# microLift.net
KiCad netlist of a schematic drawn in EAGLE
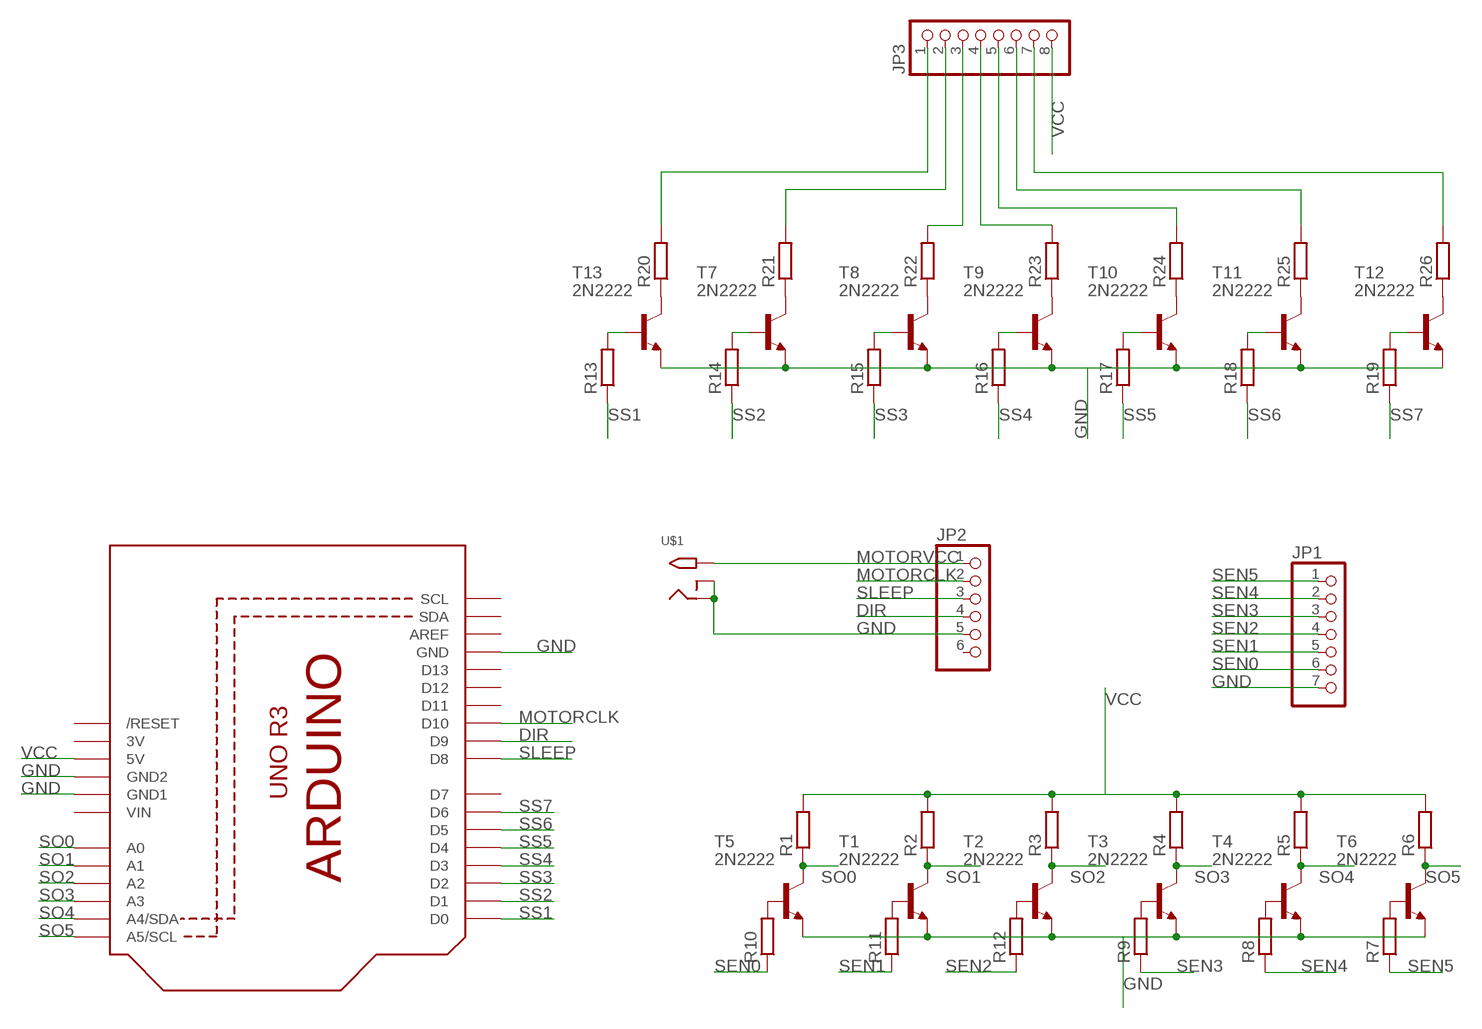
[diagram p0: schematic, sheet 1]

(export (version "E")
  (design (tool "Eeschema 10.0.6"))
  (components
    (comp (ref "JP1")
      (value "PINHD-1X7")
      (footprint "eagle-import:1X07")
      (libsource (lib "eagle-import") (part "PINHD-1X7"))
    )
    (comp (ref "JP2")
      (value "PINHD-1X6")
      (footprint "eagle-import:1X06")
      (libsource (lib "eagle-import") (part "PINHD-1X6"))
    )
    (comp (ref "JP3")
      (value "PINHD-1X8BIG")
      (footprint "eagle-import:1X08-BIG")
      (libsource (lib "eagle-import") (part "PINHD-1X8BIG"))
    )
    (comp (ref "Q1")
      (value "ARDUINOR3-NOIOREF-NOTEXT")
      (footprint "eagle-import:ARDUINOR3-NOTEXT-NOIOREF")
      (libsource (lib "eagle-import") (part "ARDUINOR3-NOIOREF-NOTEXT"))
    )
    (comp (ref "R1")
      (value "R-EU_0204/7")
      (footprint "eagle-import:0204_7")
      (libsource (lib "eagle-import") (part "R-EU_0204/7"))
    )
    (comp (ref "R2")
      (value "R-EU_0204/7")
      (footprint "eagle-import:0204_7")
      (libsource (lib "eagle-import") (part "R-EU_0204/7"))
    )
    (comp (ref "R3")
      (value "R-EU_0204/7")
      (footprint "eagle-import:0204_7")
      (libsource (lib "eagle-import") (part "R-EU_0204/7"))
    )
    (comp (ref "R4")
      (value "R-EU_0204/7")
      (footprint "eagle-import:0204_7")
      (libsource (lib "eagle-import") (part "R-EU_0204/7"))
    )
    (comp (ref "R5")
      (value "R-EU_0204/7")
      (footprint "eagle-import:0204_7")
      (libsource (lib "eagle-import") (part "R-EU_0204/7"))
    )
    (comp (ref "R6")
      (value "R-EU_0204/7")
      (footprint "eagle-import:0204_7")
      (libsource (lib "eagle-import") (part "R-EU_0204/7"))
    )
    (comp (ref "R7")
      (value "R-EU_0204/7")
      (footprint "eagle-import:0204_7")
      (libsource (lib "eagle-import") (part "resistor_R-EU_0204/7"))
    )
    (comp (ref "R8")
      (value "R-EU_0204/7")
      (footprint "eagle-import:0204_7")
      (libsource (lib "eagle-import") (part "resistor_R-EU_0204/7"))
    )
    (comp (ref "R9")
      (value "R-EU_0204/7")
      (footprint "eagle-import:0204_7")
      (libsource (lib "eagle-import") (part "resistor_R-EU_0204/7"))
    )
    (comp (ref "R10")
      (value "R-EU_0204/7")
      (footprint "eagle-import:0204_7")
      (libsource (lib "eagle-import") (part "resistor_R-EU_0204/7"))
    )
    (comp (ref "R11")
      (value "R-EU_0204/7")
      (footprint "eagle-import:0204_7")
      (libsource (lib "eagle-import") (part "resistor_R-EU_0204/7"))
    )
    (comp (ref "R12")
      (value "R-EU_0204/7")
      (footprint "eagle-import:0204_7")
      (libsource (lib "eagle-import") (part "resistor_R-EU_0204/7"))
    )
    (comp (ref "R13")
      (value "R-EU_0204/7")
      (footprint "eagle-import:0204_7")
      (libsource (lib "eagle-import") (part "R-EU_0204/7"))
    )
    (comp (ref "R14")
      (value "R-EU_0204/7")
      (footprint "eagle-import:0204_7")
      (libsource (lib "eagle-import") (part "R-EU_0204/7"))
    )
    (comp (ref "R15")
      (value "R-EU_0204/7")
      (footprint "eagle-import:0204_7")
      (libsource (lib "eagle-import") (part "R-EU_0204/7"))
    )
    (comp (ref "R16")
      (value "R-EU_0204/7")
      (footprint "eagle-import:0204_7")
      (libsource (lib "eagle-import") (part "R-EU_0204/7"))
    )
    (comp (ref "R17")
      (value "R-EU_0204/7")
      (footprint "eagle-import:0204_7")
      (libsource (lib "eagle-import") (part "R-EU_0204/7"))
    )
    (comp (ref "R18")
      (value "R-EU_0204/7")
      (footprint "eagle-import:0204_7")
      (libsource (lib "eagle-import") (part "R-EU_0204/7"))
    )
    (comp (ref "R19")
      (value "R-EU_0204/7")
      (footprint "eagle-import:0204_7")
      (libsource (lib "eagle-import") (part "R-EU_0204/7"))
    )
    (comp (ref "R20")
      (value "R-EU_0204/7")
      (footprint "eagle-import:0204_7")
      (libsource (lib "eagle-import") (part "R-EU_0204/7"))
    )
    (comp (ref "R21")
      (value "R-EU_0204/7")
      (footprint "eagle-import:0204_7")
      (libsource (lib "eagle-import") (part "R-EU_0204/7"))
    )
    (comp (ref "R22")
      (value "R-EU_0204/7")
      (footprint "eagle-import:0204_7")
      (libsource (lib "eagle-import") (part "R-EU_0204/7"))
    )
    (comp (ref "R23")
      (value "R-EU_0204/7")
      (footprint "eagle-import:0204_7")
      (libsource (lib "eagle-import") (part "R-EU_0204/7"))
    )
    (comp (ref "R24")
      (value "R-EU_0204/7")
      (footprint "eagle-import:0204_7")
      (libsource (lib "eagle-import") (part "R-EU_0204/7"))
    )
    (comp (ref "R25")
      (value "R-EU_0204/7")
      (footprint "eagle-import:0204_7")
      (libsource (lib "eagle-import") (part "R-EU_0204/7"))
    )
    (comp (ref "R26")
      (value "R-EU_0204/7")
      (footprint "eagle-import:0204_7")
      (libsource (lib "eagle-import") (part "R-EU_0204/7"))
    )
    (comp (ref "T1")
      (value "2N2222")
      (footprint "eagle-import:TO92-EBC-OVAL")
      (libsource (lib "eagle-import") (part "2N2222"))
    )
    (comp (ref "T2")
      (value "2N2222")
      (footprint "eagle-import:TO92-EBC-OVAL")
      (libsource (lib "eagle-import") (part "2N2222"))
    )
    (comp (ref "T3")
      (value "2N2222")
      (footprint "eagle-import:TO92-EBC-OVAL")
      (libsource (lib "eagle-import") (part "2N2222"))
    )
    (comp (ref "T4")
      (value "2N2222")
      (footprint "eagle-import:TO92-EBC-OVAL")
      (libsource (lib "eagle-import") (part "2N2222"))
    )
    (comp (ref "T5")
      (value "2N2222")
      (footprint "eagle-import:TO92-EBC-OVAL")
      (libsource (lib "eagle-import") (part "2N2222"))
    )
    (comp (ref "T6")
      (value "2N2222")
      (footprint "eagle-import:TO92-EBC-OVAL")
      (libsource (lib "eagle-import") (part "2N2222"))
    )
    (comp (ref "T7")
      (value "2N2222")
      (footprint "eagle-import:TO92-EBC-OVAL")
      (libsource (lib "eagle-import") (part "2N2222"))
    )
    (comp (ref "T8")
      (value "2N2222")
      (footprint "eagle-import:TO92-EBC-OVAL")
      (libsource (lib "eagle-import") (part "2N2222"))
    )
    (comp (ref "T9")
      (value "2N2222")
      (footprint "eagle-import:TO92-EBC-OVAL")
      (libsource (lib "eagle-import") (part "2N2222"))
    )
    (comp (ref "T10")
      (value "2N2222")
      (footprint "eagle-import:TO92-EBC-OVAL")
      (libsource (lib "eagle-import") (part "2N2222"))
    )
    (comp (ref "T11")
      (value "2N2222")
      (footprint "eagle-import:TO92-EBC-OVAL")
      (libsource (lib "eagle-import") (part "2N2222"))
    )
    (comp (ref "T12")
      (value "2N2222")
      (footprint "eagle-import:TO92-EBC-OVAL")
      (libsource (lib "eagle-import") (part "2N2222"))
    )
    (comp (ref "T13")
      (value "2N2222")
      (footprint "eagle-import:TO92-EBC-OVAL")
      (libsource (lib "eagle-import") (part "2N2222"))
    )
    (comp (ref "U$1")
      (value "2.1MMJACKTHM")
      (footprint "eagle-import:PJ-102A")
      (libsource (lib "eagle-import") (part "2.1MMJACKTHM"))
    )
  )
  (nets
    (net (code "1") (name "/3V") (class "Default")
      (node (ref "Q1") (pin "3V") (pinfunction "3V_3V") (pintype "power_in"))
    )
    (net (code "2") (name "/DIR") (class "Default")
      (node (ref "JP2") (pin "4") (pinfunction "4_4") (pintype "passive"))
      (node (ref "Q1") (pin "D9") (pinfunction "D9_D9") (pintype "bidirectional"))
    )
    (net (code "3") (name "/GND") (class "Default")
      (node (ref "JP1") (pin "7") (pinfunction "7_7") (pintype "passive"))
      (node (ref "JP2") (pin "5") (pinfunction "5_5") (pintype "passive"))
      (node (ref "Q1") (pin "GND") (pinfunction "GND_GND") (pintype "power_in"))
      (node (ref "Q1") (pin "GND1") (pinfunction "GND1_GND1") (pintype "power_in"))
      (node (ref "Q1") (pin "GND2") (pinfunction "GND2_GND2") (pintype "power_in"))
      (node (ref "T1") (pin "E") (pinfunction "E_E") (pintype "passive"))
      (node (ref "T10") (pin "E") (pinfunction "E_E") (pintype "passive"))
      (node (ref "T11") (pin "E") (pinfunction "E_E") (pintype "passive"))
      (node (ref "T12") (pin "E") (pinfunction "E_E") (pintype "passive"))
      (node (ref "T13") (pin "E") (pinfunction "E_E") (pintype "passive"))
      (node (ref "T2") (pin "E") (pinfunction "E_E") (pintype "passive"))
      (node (ref "T3") (pin "E") (pinfunction "E_E") (pintype "passive"))
      (node (ref "T4") (pin "E") (pinfunction "E_E") (pintype "passive"))
      (node (ref "T5") (pin "E") (pinfunction "E_E") (pintype "passive"))
      (node (ref "T6") (pin "E") (pinfunction "E_E") (pintype "passive"))
      (node (ref "T7") (pin "E") (pinfunction "E_E") (pintype "passive"))
      (node (ref "T8") (pin "E") (pinfunction "E_E") (pintype "passive"))
      (node (ref "T9") (pin "E") (pinfunction "E_E") (pintype "passive"))
      (node (ref "U$1") (pin "RING") (pinfunction "RING_RING") (pintype "bidirectional"))
      (node (ref "U$1") (pin "RING_SW") (pinfunction "RING_SW_RING_SW") (pintype "bidirectional"))
    )
    (net (code "4") (name "/MOTORCLK") (class "Default")
      (node (ref "JP2") (pin "2") (pinfunction "2_2") (pintype "passive"))
      (node (ref "Q1") (pin "D10") (pinfunction "D10_D10") (pintype "bidirectional"))
    )
    (net (code "5") (name "/MOTORVCC") (class "Default")
      (node (ref "JP2") (pin "1") (pinfunction "1_1") (pintype "passive"))
      (node (ref "U$1") (pin "TIP") (pinfunction "TIP_TIP") (pintype "bidirectional"))
    )
    (net (code "6") (name "/SEN0") (class "Default")
      (node (ref "JP1") (pin "6") (pinfunction "6_6") (pintype "passive"))
      (node (ref "R10") (pin "1") (pinfunction "1_1") (pintype "passive"))
    )
    (net (code "7") (name "/SEN1") (class "Default")
      (node (ref "JP1") (pin "5") (pinfunction "5_5") (pintype "passive"))
      (node (ref "R11") (pin "1") (pinfunction "1_1") (pintype "passive"))
    )
    (net (code "8") (name "/SEN2") (class "Default")
      (node (ref "JP1") (pin "4") (pinfunction "4_4") (pintype "passive"))
      (node (ref "R12") (pin "1") (pinfunction "1_1") (pintype "passive"))
    )
    (net (code "9") (name "/SEN3") (class "Default")
      (node (ref "JP1") (pin "3") (pinfunction "3_3") (pintype "passive"))
      (node (ref "R9") (pin "1") (pinfunction "1_1") (pintype "passive"))
    )
    (net (code "10") (name "/SEN4") (class "Default")
      (node (ref "JP1") (pin "2") (pinfunction "2_2") (pintype "passive"))
      (node (ref "R8") (pin "1") (pinfunction "1_1") (pintype "passive"))
    )
    (net (code "11") (name "/SEN5") (class "Default")
      (node (ref "JP1") (pin "1") (pinfunction "1_1") (pintype "passive"))
      (node (ref "R7") (pin "1") (pinfunction "1_1") (pintype "passive"))
    )
    (net (code "12") (name "/SLEEP") (class "Default")
      (node (ref "JP2") (pin "3") (pinfunction "3_3") (pintype "passive"))
      (node (ref "Q1") (pin "D8") (pinfunction "D8_D8") (pintype "bidirectional"))
    )
    (net (code "13") (name "/SO0") (class "Default")
      (node (ref "Q1") (pin "A0") (pinfunction "A0_A0") (pintype "bidirectional"))
      (node (ref "R1") (pin "1") (pinfunction "1_1") (pintype "passive"))
      (node (ref "T5") (pin "C") (pinfunction "C_C") (pintype "passive"))
    )
    (net (code "14") (name "/SO1") (class "Default")
      (node (ref "Q1") (pin "A1") (pinfunction "A1_A1") (pintype "bidirectional"))
      (node (ref "R2") (pin "1") (pinfunction "1_1") (pintype "passive"))
      (node (ref "T1") (pin "C") (pinfunction "C_C") (pintype "passive"))
    )
    (net (code "15") (name "/SO2") (class "Default")
      (node (ref "Q1") (pin "A2") (pinfunction "A2_A2") (pintype "bidirectional"))
      (node (ref "R3") (pin "1") (pinfunction "1_1") (pintype "passive"))
      (node (ref "T2") (pin "C") (pinfunction "C_C") (pintype "passive"))
    )
    (net (code "16") (name "/SO3") (class "Default")
      (node (ref "Q1") (pin "A3") (pinfunction "A3_A3") (pintype "bidirectional"))
      (node (ref "R4") (pin "1") (pinfunction "1_1") (pintype "passive"))
      (node (ref "T3") (pin "C") (pinfunction "C_C") (pintype "passive"))
    )
    (net (code "17") (name "/SO4") (class "Default")
      (node (ref "Q1") (pin "A4") (pinfunction "A4/SDA_A4") (pintype "bidirectional"))
      (node (ref "R5") (pin "1") (pinfunction "1_1") (pintype "passive"))
      (node (ref "T4") (pin "C") (pinfunction "C_C") (pintype "passive"))
    )
    (net (code "18") (name "/SO5") (class "Default")
      (node (ref "Q1") (pin "A5") (pinfunction "A5/SCL_A5") (pintype "bidirectional"))
      (node (ref "R6") (pin "1") (pinfunction "1_1") (pintype "passive"))
      (node (ref "T6") (pin "C") (pinfunction "C_C") (pintype "passive"))
    )
    (net (code "19") (name "/SS1") (class "Default")
      (node (ref "Q1") (pin "D0") (pinfunction "D0_D0") (pintype "bidirectional"))
      (node (ref "R13") (pin "1") (pinfunction "1_1") (pintype "passive"))
    )
    (net (code "20") (name "/SS2") (class "Default")
      (node (ref "Q1") (pin "D1") (pinfunction "D1_D1") (pintype "bidirectional"))
      (node (ref "R14") (pin "1") (pinfunction "1_1") (pintype "passive"))
    )
    (net (code "21") (name "/SS3") (class "Default")
      (node (ref "Q1") (pin "D2") (pinfunction "D2_D2") (pintype "bidirectional"))
      (node (ref "R15") (pin "1") (pinfunction "1_1") (pintype "passive"))
    )
    (net (code "22") (name "/SS4") (class "Default")
      (node (ref "Q1") (pin "D3") (pinfunction "D3_D3") (pintype "bidirectional"))
      (node (ref "R16") (pin "1") (pinfunction "1_1") (pintype "passive"))
    )
    (net (code "23") (name "/SS5") (class "Default")
      (node (ref "Q1") (pin "D4") (pinfunction "D4_D4") (pintype "bidirectional"))
      (node (ref "R17") (pin "1") (pinfunction "1_1") (pintype "passive"))
    )
    (net (code "24") (name "/SS6") (class "Default")
      (node (ref "Q1") (pin "D5") (pinfunction "D5_D5") (pintype "bidirectional"))
      (node (ref "R18") (pin "1") (pinfunction "1_1") (pintype "passive"))
    )
    (net (code "25") (name "/SS7") (class "Default")
      (node (ref "Q1") (pin "D6") (pinfunction "D6_D6") (pintype "bidirectional"))
      (node (ref "R19") (pin "1") (pinfunction "1_1") (pintype "passive"))
    )
    (net (code "26") (name "/VCC") (class "Default")
      (node (ref "JP3") (pin "8") (pinfunction "8_8") (pintype "passive"))
      (node (ref "Q1") (pin "5V") (pinfunction "5V_5V") (pintype "power_in"))
      (node (ref "R1") (pin "2") (pinfunction "2_2") (pintype "passive"))
      (node (ref "R2") (pin "2") (pinfunction "2_2") (pintype "passive"))
      (node (ref "R3") (pin "2") (pinfunction "2_2") (pintype "passive"))
      (node (ref "R4") (pin "2") (pinfunction "2_2") (pintype "passive"))
      (node (ref "R5") (pin "2") (pinfunction "2_2") (pintype "passive"))
      (node (ref "R6") (pin "2") (pinfunction "2_2") (pintype "passive"))
    )
    (net (code "27") (name "/VIN") (class "Default")
      (node (ref "Q1") (pin "VIN") (pinfunction "VIN_VIN") (pintype "power_in"))
    )
    (net (code "28") (name "Net-(JP3-Pad1)") (class "Default")
      (node (ref "JP3") (pin "1") (pinfunction "1_1") (pintype "passive"))
      (node (ref "R20") (pin "2") (pinfunction "2_2") (pintype "passive"))
    )
    (net (code "29") (name "Net-(JP3-Pad2)") (class "Default")
      (node (ref "JP3") (pin "2") (pinfunction "2_2") (pintype "passive"))
      (node (ref "R21") (pin "2") (pinfunction "2_2") (pintype "passive"))
    )
    (net (code "30") (name "Net-(JP3-Pad3)") (class "Default")
      (node (ref "JP3") (pin "3") (pinfunction "3_3") (pintype "passive"))
      (node (ref "R22") (pin "2") (pinfunction "2_2") (pintype "passive"))
    )
    (net (code "31") (name "Net-(JP3-Pad4)") (class "Default")
      (node (ref "JP3") (pin "4") (pinfunction "4_4") (pintype "passive"))
      (node (ref "R23") (pin "2") (pinfunction "2_2") (pintype "passive"))
    )
    (net (code "32") (name "Net-(JP3-Pad5)") (class "Default")
      (node (ref "JP3") (pin "5") (pinfunction "5_5") (pintype "passive"))
      (node (ref "R24") (pin "2") (pinfunction "2_2") (pintype "passive"))
    )
    (net (code "33") (name "Net-(JP3-Pad6)") (class "Default")
      (node (ref "JP3") (pin "6") (pinfunction "6_6") (pintype "passive"))
      (node (ref "R25") (pin "2") (pinfunction "2_2") (pintype "passive"))
    )
    (net (code "34") (name "Net-(JP3-Pad7)") (class "Default")
      (node (ref "JP3") (pin "7") (pinfunction "7_7") (pintype "passive"))
      (node (ref "R26") (pin "2") (pinfunction "2_2") (pintype "passive"))
    )
    (net (code "35") (name "Net-(R7-Pad2)") (class "Default")
      (node (ref "R7") (pin "2") (pinfunction "2_2") (pintype "passive"))
      (node (ref "T6") (pin "B") (pinfunction "B_B") (pintype "passive"))
    )
    (net (code "36") (name "Net-(R8-Pad2)") (class "Default")
      (node (ref "R8") (pin "2") (pinfunction "2_2") (pintype "passive"))
      (node (ref "T4") (pin "B") (pinfunction "B_B") (pintype "passive"))
    )
    (net (code "37") (name "Net-(R9-Pad2)") (class "Default")
      (node (ref "R9") (pin "2") (pinfunction "2_2") (pintype "passive"))
      (node (ref "T3") (pin "B") (pinfunction "B_B") (pintype "passive"))
    )
    (net (code "38") (name "Net-(R10-Pad2)") (class "Default")
      (node (ref "R10") (pin "2") (pinfunction "2_2") (pintype "passive"))
      (node (ref "T5") (pin "B") (pinfunction "B_B") (pintype "passive"))
    )
    (net (code "39") (name "Net-(R11-Pad2)") (class "Default")
      (node (ref "R11") (pin "2") (pinfunction "2_2") (pintype "passive"))
      (node (ref "T1") (pin "B") (pinfunction "B_B") (pintype "passive"))
    )
    (net (code "40") (name "Net-(R12-Pad2)") (class "Default")
      (node (ref "R12") (pin "2") (pinfunction "2_2") (pintype "passive"))
      (node (ref "T2") (pin "B") (pinfunction "B_B") (pintype "passive"))
    )
    (net (code "41") (name "Net-(R13-Pad2)") (class "Default")
      (node (ref "R13") (pin "2") (pinfunction "2_2") (pintype "passive"))
      (node (ref "T13") (pin "B") (pinfunction "B_B") (pintype "passive"))
    )
    (net (code "42") (name "Net-(R14-Pad2)") (class "Default")
      (node (ref "R14") (pin "2") (pinfunction "2_2") (pintype "passive"))
      (node (ref "T7") (pin "B") (pinfunction "B_B") (pintype "passive"))
    )
    (net (code "43") (name "Net-(R15-Pad2)") (class "Default")
      (node (ref "R15") (pin "2") (pinfunction "2_2") (pintype "passive"))
      (node (ref "T8") (pin "B") (pinfunction "B_B") (pintype "passive"))
    )
    (net (code "44") (name "Net-(R16-Pad2)") (class "Default")
      (node (ref "R16") (pin "2") (pinfunction "2_2") (pintype "passive"))
      (node (ref "T9") (pin "B") (pinfunction "B_B") (pintype "passive"))
    )
    (net (code "45") (name "Net-(R17-Pad2)") (class "Default")
      (node (ref "R17") (pin "2") (pinfunction "2_2") (pintype "passive"))
      (node (ref "T10") (pin "B") (pinfunction "B_B") (pintype "passive"))
    )
    (net (code "46") (name "Net-(R18-Pad2)") (class "Default")
      (node (ref "R18") (pin "2") (pinfunction "2_2") (pintype "passive"))
      (node (ref "T11") (pin "B") (pinfunction "B_B") (pintype "passive"))
    )
    (net (code "47") (name "Net-(R19-Pad2)") (class "Default")
      (node (ref "R19") (pin "2") (pinfunction "2_2") (pintype "passive"))
      (node (ref "T12") (pin "B") (pinfunction "B_B") (pintype "passive"))
    )
    (net (code "48") (name "Net-(R20-Pad1)") (class "Default")
      (node (ref "R20") (pin "1") (pinfunction "1_1") (pintype "passive"))
      (node (ref "T13") (pin "C") (pinfunction "C_C") (pintype "passive"))
    )
    (net (code "49") (name "Net-(R21-Pad1)") (class "Default")
      (node (ref "R21") (pin "1") (pinfunction "1_1") (pintype "passive"))
      (node (ref "T7") (pin "C") (pinfunction "C_C") (pintype "passive"))
    )
    (net (code "50") (name "Net-(R22-Pad1)") (class "Default")
      (node (ref "R22") (pin "1") (pinfunction "1_1") (pintype "passive"))
      (node (ref "T8") (pin "C") (pinfunction "C_C") (pintype "passive"))
    )
    (net (code "51") (name "Net-(R23-Pad1)") (class "Default")
      (node (ref "R23") (pin "1") (pinfunction "1_1") (pintype "passive"))
      (node (ref "T9") (pin "C") (pinfunction "C_C") (pintype "passive"))
    )
    (net (code "52") (name "Net-(R24-Pad1)") (class "Default")
      (node (ref "R24") (pin "1") (pinfunction "1_1") (pintype "passive"))
      (node (ref "T10") (pin "C") (pinfunction "C_C") (pintype "passive"))
    )
    (net (code "53") (name "Net-(R25-Pad1)") (class "Default")
      (node (ref "R25") (pin "1") (pinfunction "1_1") (pintype "passive"))
      (node (ref "T11") (pin "C") (pinfunction "C_C") (pintype "passive"))
    )
    (net (code "54") (name "Net-(R26-Pad1)") (class "Default")
      (node (ref "R26") (pin "1") (pinfunction "1_1") (pintype "passive"))
      (node (ref "T12") (pin "C") (pinfunction "C_C") (pintype "passive"))
    )
    (net (code "55") (name "unconnected-(JP2-Pad6)") (class "Default")
      (node (ref "JP2") (pin "6") (pinfunction "6_6") (pintype "passive"))
    )
    (net (code "56") (name "unconnected-(Q1-PadAREF)") (class "Default")
      (node (ref "Q1") (pin "AREF") (pinfunction "AREF_AREF") (pintype "bidirectional"))
    )
    (net (code "57") (name "unconnected-(Q1-PadD7)") (class "Default")
      (node (ref "Q1") (pin "D7") (pinfunction "D7_D7") (pintype "bidirectional"))
    )
    (net (code "58") (name "unconnected-(Q1-PadD11)") (class "Default")
      (node (ref "Q1") (pin "D11") (pinfunction "D11_D11") (pintype "bidirectional"))
    )
    (net (code "59") (name "unconnected-(Q1-PadD12)") (class "Default")
      (node (ref "Q1") (pin "D12") (pinfunction "D12_D12") (pintype "bidirectional"))
    )
    (net (code "60") (name "unconnected-(Q1-PadD13)") (class "Default")
      (node (ref "Q1") (pin "D13") (pinfunction "D13_D13") (pintype "bidirectional"))
    )
    (net (code "61") (name "unconnected-(Q1-PadSCL)") (class "Default")
      (node (ref "Q1") (pin "SCL") (pinfunction "SCL_SCL") (pintype "bidirectional"))
    )
    (net (code "62") (name "unconnected-(Q1-PadSDA)") (class "Default")
      (node (ref "Q1") (pin "SDA") (pinfunction "SDA_SDA") (pintype "bidirectional"))
    )
    (net (code "63") (name "unconnected-(Q1-{slash}RESET-PadRESET)") (class "Default")
      (node (ref "Q1") (pin "RESET") (pinfunction "/RESET_RESET") (pintype "bidirectional"))
    )
  )
)
